# piezo-preamp-tickler-buffer-only-V0.net
KiCad netlist of a schematic drawn in EAGLE
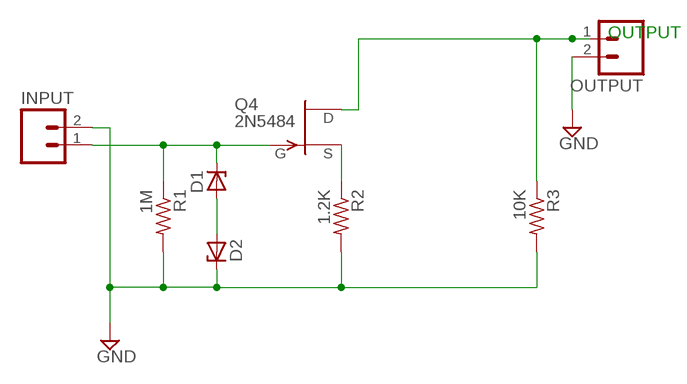
[diagram p0: schematic, sheet 1]

(export (version "E")
  (design (tool "Eeschema 10.0.6"))
  (components
    (comp (ref "D1")
      (value "1N821")
      (footprint "eagle-import:DO35Z10")
      (libsource (lib "eagle-import") (part "1N821"))
    )
    (comp (ref "D2")
      (value "1N821")
      (footprint "eagle-import:DO35Z10")
      (libsource (lib "eagle-import") (part "1N821"))
    )
    (comp (ref "INPUT")
      (value "M02LOCK")
      (footprint "eagle-import:1X02_LOCK")
      (libsource (lib "eagle-import") (part "M02LOCK"))
    )
    (comp (ref "OUTPUT")
      (value "M02LOCK")
      (footprint "eagle-import:1X02_LOCK")
      (libsource (lib "eagle-import") (part "M02LOCK"))
    )
    (comp (ref "Q4")
      (value "2N5484")
      (footprint "eagle-import:TO92-")
      (libsource (lib "eagle-import") (part "?5482N4"))
    )
    (comp (ref "R1")
      (value "1M")
      (footprint "eagle-import:VMTA55")
      (libsource (lib "eagle-import") (part "R-US_VMTA55"))
    )
    (comp (ref "R2")
      (value "1.2K")
      (footprint "eagle-import:VMTA55")
      (libsource (lib "eagle-import") (part "R-US_VMTA55"))
    )
    (comp (ref "R3")
      (value "10K")
      (footprint "eagle-import:VMTA55")
      (libsource (lib "eagle-import") (part "R-US_VMTA55"))
    )
  )
  (nets
    (net (code "1") (name "GND") (class "Default")
      (node (ref "D2") (pin "C") (pinfunction "C_C") (pintype "passive"))
      (node (ref "INPUT") (pin "2") (pinfunction "2_2") (pintype "passive"))
      (node (ref "OUTPUT") (pin "2") (pinfunction "2_2") (pintype "passive"))
      (node (ref "R1") (pin "2") (pinfunction "2_2") (pintype "passive"))
      (node (ref "R2") (pin "2") (pinfunction "2_2") (pintype "passive"))
      (node (ref "R3") (pin "2") (pinfunction "2_2") (pintype "passive"))
    )
    (net (code "2") (name "Net-(D1-PadA)") (class "Default")
      (node (ref "D1") (pin "A") (pinfunction "A_A") (pintype "passive"))
      (node (ref "D2") (pin "A") (pinfunction "A_A") (pintype "passive"))
    )
    (net (code "3") (name "Net-(Q4-D)") (class "Default")
      (node (ref "OUTPUT") (pin "1") (pinfunction "1_1") (pintype "passive"))
      (node (ref "Q4") (pin "3") (pinfunction "D_3") (pintype "passive"))
      (node (ref "R3") (pin "1") (pinfunction "1_1") (pintype "passive"))
    )
    (net (code "4") (name "Net-(Q4-G)") (class "Default")
      (node (ref "D1") (pin "C") (pinfunction "C_C") (pintype "passive"))
      (node (ref "INPUT") (pin "1") (pinfunction "1_1") (pintype "passive"))
      (node (ref "Q4") (pin "1") (pinfunction "G_1") (pintype "passive"))
      (node (ref "R1") (pin "1") (pinfunction "1_1") (pintype "passive"))
    )
    (net (code "5") (name "Net-(Q4-S)") (class "Default")
      (node (ref "Q4") (pin "2") (pinfunction "S_2") (pintype "passive"))
      (node (ref "R2") (pin "1") (pinfunction "1_1") (pintype "passive"))
    )
  )
)
